# 120-12V-DCDC.net
KiCad netlist of a schematic drawn in Altium Designer
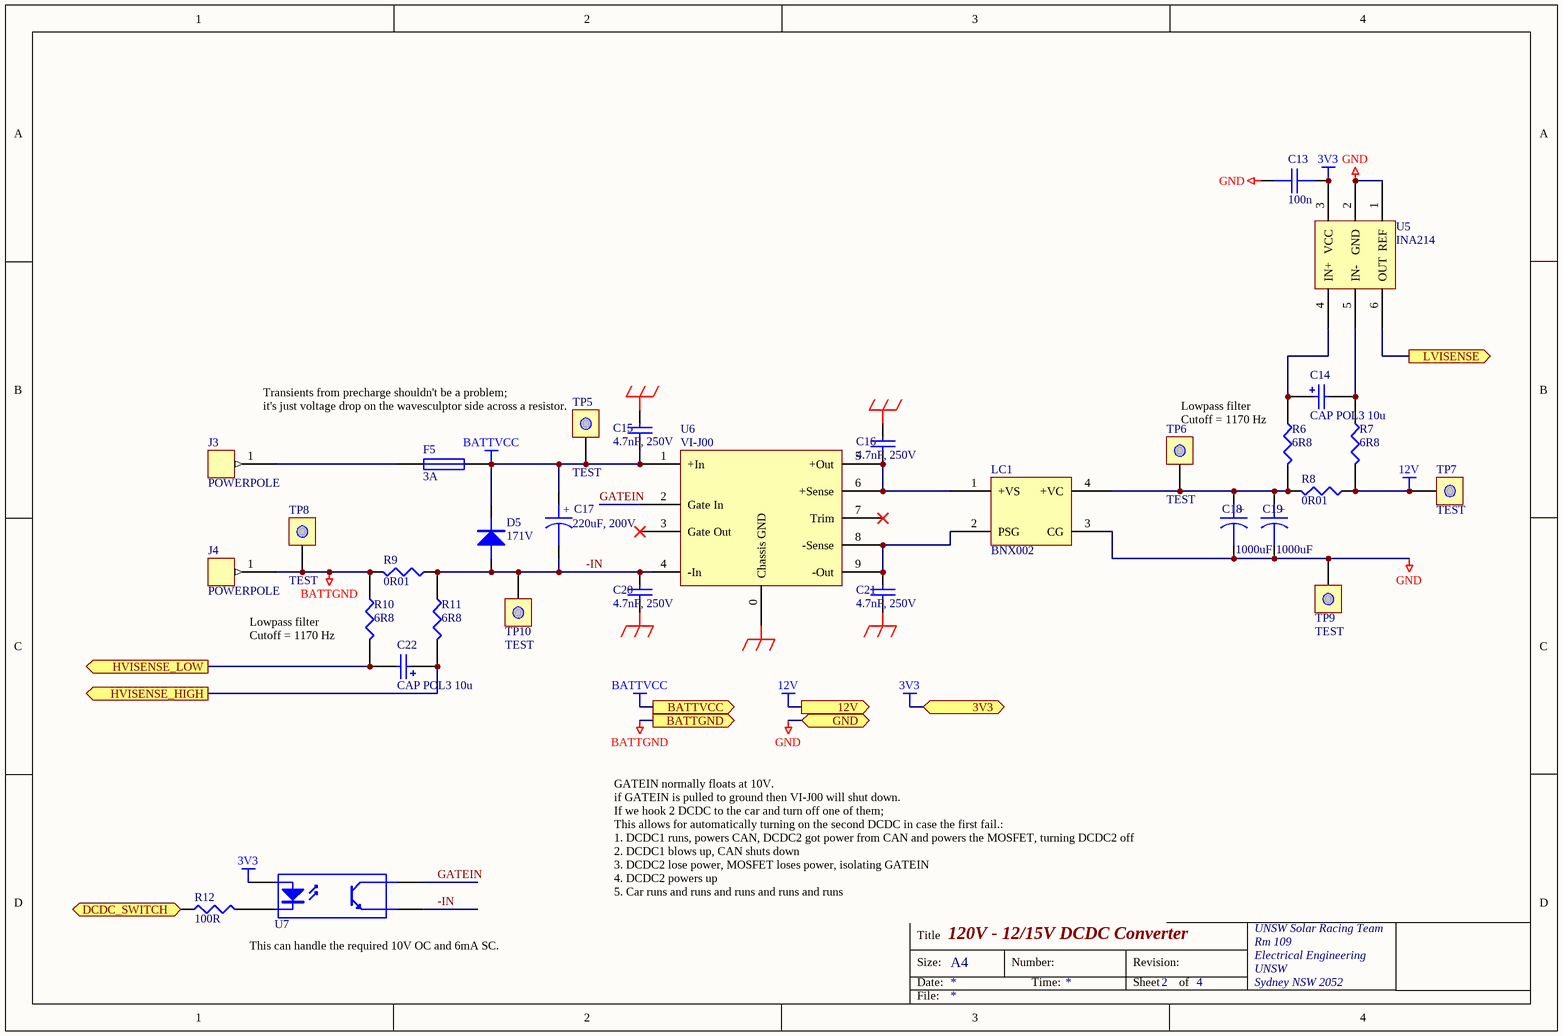
[diagram p0: 120-12V-DCDC.SCHDOC]

(export (version "E")
  (design (tool "Eeschema 10.0.6"))
  (components
    (comp (ref "C13")
      (value "100n")
      (footprint "0603")
      (description "Capacitor")
      (libsource (lib "") (part "CAP_1"))
    )
    (comp (ref "C14")
      (value "CAP POL3 10u")
      (footprint "MCCT-CASEA")
      (description "Polarized Capacitor (Surface Mount)")
      (libsource (lib "RCLDQ") (part "CAP POL3"))
    )
    (comp (ref "C15")
      (value "4.7nF, 250V")
      (footprint "POLYESTER-5")
      (description "Capacitor")
      (libsource (lib "*") (part "CAP"))
    )
    (comp (ref "C16")
      (value "4.7nF, 250V")
      (footprint "POLYESTER-5")
      (description "Capacitor")
      (libsource (lib "*") (part "CAP"))
    )
    (comp (ref "C17")
      (value "220uF, 200V")
      (footprint "ELECTROLYTIC-10-20")
      (description "Capacitor")
      (libsource (lib "*") (part "CAPACITOR POL"))
    )
    (comp (ref "C18")
      (value "1000uF")
      (footprint "ELECTROLYTIC-5-10")
      (description "Capacitor")
      (libsource (lib "*") (part "CAPACITOR POL"))
    )
    (comp (ref "C19")
      (value "1000uF")
      (footprint "ELECTROLYTIC-5-10")
      (description "Capacitor")
      (libsource (lib "*") (part "CAPACITOR POL"))
    )
    (comp (ref "C20")
      (value "4.7nF, 250V")
      (footprint "POLYESTER-5")
      (description "Capacitor")
      (libsource (lib "*") (part "CAP"))
    )
    (comp (ref "C21")
      (value "4.7nF, 250V")
      (footprint "POLYESTER-5")
      (description "Capacitor")
      (libsource (lib "*") (part "CAP"))
    )
    (comp (ref "C22")
      (value "CAP POL3 10u")
      (footprint "MCCT-CASEA")
      (description "Polarized Capacitor (Surface Mount)")
      (libsource (lib "RCLDQ") (part "CAP POL3"))
    )
    (comp (ref "D5")
      (value "171V")
      (footprint "DIODE-D1.2mm")
      (description "Diode")
      (libsource (lib "RCLDQ") (part "DIODE"))
    )
    (comp (ref "F5")
      (value "3A")
      (footprint "FUSE-BAYONET-RA")
      (description "Fuse")
      (libsource (lib "*") (part "FUSE1"))
    )
    (comp (ref "J3")
      (value "POWERPOLE")
      (footprint "POWERPOLE25A")
      (libsource (lib "Connectors") (part "CON1"))
    )
    (comp (ref "J4")
      (value "POWERPOLE")
      (footprint "POWERPOLE25A")
      (libsource (lib "Connectors") (part "CON1"))
    )
    (comp (ref "LC1")
      (value "BNX002")
      (footprint "BNX002")
      (description "10A Switchmode Supply Output Filter")
      (libsource (lib "*") (part "BNX002"))
    )
    (comp (ref "R6") (value "6R8") (footprint "0603") (libsource (lib "*") (part "RES1")))
    (comp (ref "R7") (value "6R8") (footprint "0603") (libsource (lib "*") (part "RES1")))
    (comp (ref "R8")
      (value "0R01")
      (footprint "CRA2512")
      (description "Current Sense Resistor")
      (libsource (lib "RCLDQ") (part "CRA2512"))
    )
    (comp (ref "R9")
      (value "0R01")
      (footprint "CRA2512")
      (description "Current Sense Resistor")
      (libsource (lib "RCLDQ") (part "CRA2512"))
    )
    (comp (ref "R10") (value "6R8") (footprint "0603") (libsource (lib "*") (part "RES1")))
    (comp (ref "R11") (value "6R8") (footprint "0603") (libsource (lib "*") (part "RES1")))
    (comp (ref "R12")
      (value "100R")
      (footprint "0603")
      (description "Resistor")
      (libsource (lib "RCLDQ") (part "RES1"))
    )
    (comp (ref "TP5")
      (value "TEST")
      (footprint "TESTPOINT")
      (description "TEST POINT")
      (libsource (lib "") (part "TEST_1"))
    )
    (comp (ref "TP6")
      (value "TEST")
      (footprint "TESTPOINT")
      (description "TEST POINT")
      (libsource (lib "") (part "TEST_1"))
    )
    (comp (ref "TP7")
      (value "TEST")
      (footprint "TESTPOINT")
      (description "TEST POINT")
      (libsource (lib "") (part "TEST_2"))
    )
    (comp (ref "TP8")
      (value "TEST")
      (footprint "TESTPOINT")
      (description "TEST POINT")
      (libsource (lib "") (part "TEST_1"))
    )
    (comp (ref "TP9")
      (value "TEST")
      (footprint "TESTPOINT")
      (description "TEST POINT")
      (libsource (lib "Miscellaneous") (part "TEST"))
    )
    (comp (ref "TP10")
      (value "TEST")
      (footprint "TESTPOINT")
      (description "TEST POINT")
      (libsource (lib "Miscellaneous") (part "TEST"))
    )
    (comp (ref "U5")
      (value "INA214")
      (footprint "SC70-6")
      (description "Current Sensor")
      (libsource (lib "MiscellaneousIC") (part "INA214"))
    )
    (comp (ref "U6")
      (value "VI-J00")
      (footprint "VI-J00")
      (description "VI-J00 Switch Mode DC-DC Converter")
      (libsource (lib "*") (part "VI-J00"))
    )
    (comp (ref "U7")
      (value "PC3H7J00000F")
      (footprint "PC3H7")
      (description "Opto-coupler")
      (libsource (lib "Optocouplers") (part "PC3H7J00000F"))
    )
  )
  (nets
    (net (code "1") (name "/-IN") (class "Default")
      (node (ref "C17") (pin "2") (pinfunction "2_2") (pintype "passive"))
      (node (ref "C20") (pin "2") (pinfunction "2_2") (pintype "passive"))
      (node (ref "D5") (pin "A") (pinfunction "A_A") (pintype "passive"))
      (node (ref "R11") (pin "1") (pinfunction "1_1") (pintype "passive"))
      (node (ref "R9") (pin "1") (pinfunction "1_1") (pintype "passive"))
      (node (ref "TP10") (pin "0") (pinfunction "TP_0") (pintype "passive"))
      (node (ref "U6") (pin "4") (pinfunction "-In_4") (pintype "passive"))
      (node (ref "U7") (pin "3") (pinfunction "E_3") (pintype "passive"))
    )
    (net (code "2") (name "/DCDC_SWITCH") (class "Default")
      (node (ref "R12") (pin "1") (pinfunction "1_1") (pintype "passive"))
    )
    (net (code "3") (name "/GATEIN") (class "Default")
      (node (ref "U6") (pin "2") (pinfunction "Gate_In_2") (pintype "passive"))
      (node (ref "U7") (pin "4") (pinfunction "C_4") (pintype "passive"))
    )
    (net (code "4") (name "/HVISENSE_HIGH") (class "Default")
      (node (ref "C22") (pin "1") (pinfunction "1_1") (pintype "passive"))
      (node (ref "R11") (pin "2") (pinfunction "2_2") (pintype "passive"))
    )
    (net (code "5") (name "/HVISENSE_LOW") (class "Default")
      (node (ref "C22") (pin "2") (pinfunction "2_2") (pintype "passive"))
      (node (ref "R10") (pin "2") (pinfunction "2_2") (pintype "passive"))
    )
    (net (code "6") (name "/LVISENSE") (class "Default")
      (node (ref "U5") (pin "6") (pinfunction "OUT_6") (pintype "passive"))
    )
    (net (code "7") (name "3V3") (class "Default")
      (node (ref "C13") (pin "2") (pinfunction "2_2") (pintype "passive"))
      (node (ref "U5") (pin "3") (pinfunction "VCC_3") (pintype "passive"))
      (node (ref "U7") (pin "1") (pinfunction "A_1") (pintype "passive"))
    )
    (net (code "8") (name "12V") (class "Default")
      (node (ref "R7") (pin "2") (pinfunction "2_2") (pintype "passive"))
      (node (ref "R8") (pin "1") (pinfunction "1_1") (pintype "passive"))
      (node (ref "TP7") (pin "0") (pinfunction "TP_0") (pintype "passive"))
    )
    (net (code "9") (name "BATTGND") (class "Default")
      (node (ref "J4") (pin "1") (pinfunction "1_1") (pintype "output"))
      (node (ref "R10") (pin "1") (pinfunction "1_1") (pintype "passive"))
      (node (ref "R9") (pin "2") (pinfunction "2_2") (pintype "passive"))
      (node (ref "TP8") (pin "0") (pinfunction "TP_0") (pintype "passive"))
    )
    (net (code "10") (name "BATTVCC") (class "Default")
      (node (ref "C15") (pin "1") (pinfunction "1_1") (pintype "passive"))
      (node (ref "C17") (pin "1") (pinfunction "1_1") (pintype "passive"))
      (node (ref "D5") (pin "K") (pinfunction "K_K") (pintype "passive"))
      (node (ref "F5") (pin "1") (pinfunction "1_1") (pintype "passive"))
      (node (ref "TP5") (pin "0") (pinfunction "TP_0") (pintype "passive"))
      (node (ref "U6") (pin "1") (pinfunction "+In_1") (pintype "passive"))
    )
    (net (code "11") (name "CGND") (class "Default")
      (node (ref "C15") (pin "2") (pinfunction "2_2") (pintype "passive"))
      (node (ref "C16") (pin "2") (pinfunction "2_2") (pintype "passive"))
      (node (ref "C20") (pin "1") (pinfunction "1_1") (pintype "passive"))
      (node (ref "C21") (pin "1") (pinfunction "1_1") (pintype "passive"))
      (node (ref "U6") (pin "0") (pinfunction "Chassis_GND_0") (pintype "passive"))
    )
    (net (code "12") (name "GND") (class "Default")
      (node (ref "C13") (pin "1") (pinfunction "1_1") (pintype "passive"))
      (node (ref "C18") (pin "2") (pinfunction "2_2") (pintype "passive"))
      (node (ref "C19") (pin "2") (pinfunction "2_2") (pintype "passive"))
      (node (ref "LC1") (pin "3") (pinfunction "CG_3") (pintype "passive"))
      (node (ref "TP9") (pin "0") (pinfunction "TP_0") (pintype "passive"))
      (node (ref "U5") (pin "1") (pinfunction "REF_1") (pintype "passive"))
      (node (ref "U5") (pin "2") (pinfunction "GND_2") (pintype "passive"))
    )
    (net (code "13") (name "Net-(F5-Pad2)") (class "Default")
      (node (ref "F5") (pin "2") (pinfunction "2_2") (pintype "passive"))
      (node (ref "J3") (pin "1") (pinfunction "1_1") (pintype "output"))
    )
    (net (code "14") (name "Net-(LC1-+VC)") (class "Default")
      (node (ref "C18") (pin "1") (pinfunction "1_1") (pintype "passive"))
      (node (ref "C19") (pin "1") (pinfunction "1_1") (pintype "passive"))
      (node (ref "LC1") (pin "4") (pinfunction "+VC_4") (pintype "passive"))
      (node (ref "R6") (pin "2") (pinfunction "2_2") (pintype "passive"))
      (node (ref "R8") (pin "2") (pinfunction "2_2") (pintype "passive"))
      (node (ref "TP6") (pin "0") (pinfunction "TP_0") (pintype "passive"))
    )
    (net (code "15") (name "Net-(LC1-+VS)") (class "Default")
      (node (ref "C16") (pin "1") (pinfunction "1_1") (pintype "passive"))
      (node (ref "LC1") (pin "1") (pinfunction "+VS_1") (pintype "passive"))
      (node (ref "U6") (pin "5") (pinfunction "+Out_5") (pintype "passive"))
      (node (ref "U6") (pin "6") (pinfunction "+Sense_6") (pintype "passive"))
    )
    (net (code "16") (name "Net-(LC1-PSG)") (class "Default")
      (node (ref "C21") (pin "2") (pinfunction "2_2") (pintype "passive"))
      (node (ref "LC1") (pin "2") (pinfunction "PSG_2") (pintype "passive"))
      (node (ref "U6") (pin "8") (pinfunction "-Sense_8") (pintype "passive"))
      (node (ref "U6") (pin "9") (pinfunction "-Out_9") (pintype "passive"))
    )
    (net (code "17") (name "Net-(U5-IN+)") (class "Default")
      (node (ref "C14") (pin "1") (pinfunction "1_1") (pintype "passive"))
      (node (ref "R6") (pin "1") (pinfunction "1_1") (pintype "passive"))
      (node (ref "U5") (pin "4") (pinfunction "IN+_4") (pintype "passive"))
    )
    (net (code "18") (name "Net-(U5-IN-)") (class "Default")
      (node (ref "C14") (pin "2") (pinfunction "2_2") (pintype "passive"))
      (node (ref "R7") (pin "1") (pinfunction "1_1") (pintype "passive"))
      (node (ref "U5") (pin "5") (pinfunction "IN-_5") (pintype "passive"))
    )
    (net (code "19") (name "Net-(U7-K)") (class "Default")
      (node (ref "R12") (pin "2") (pinfunction "2_2") (pintype "passive"))
      (node (ref "U7") (pin "2") (pinfunction "K_2") (pintype "passive"))
    )
    (net (code "20") (name "unconnected-(U6-Gate_Out-Pad3)") (class "Default")
      (node (ref "U6") (pin "3") (pinfunction "Gate_Out_3") (pintype "passive+no_connect"))
    )
    (net (code "21") (name "unconnected-(U6-Trim-Pad7)") (class "Default")
      (node (ref "U6") (pin "7") (pinfunction "Trim_7") (pintype "passive+no_connect"))
    )
  )
)
